# Reactrobe.net
KiCad netlist of a schematic drawn in EAGLE
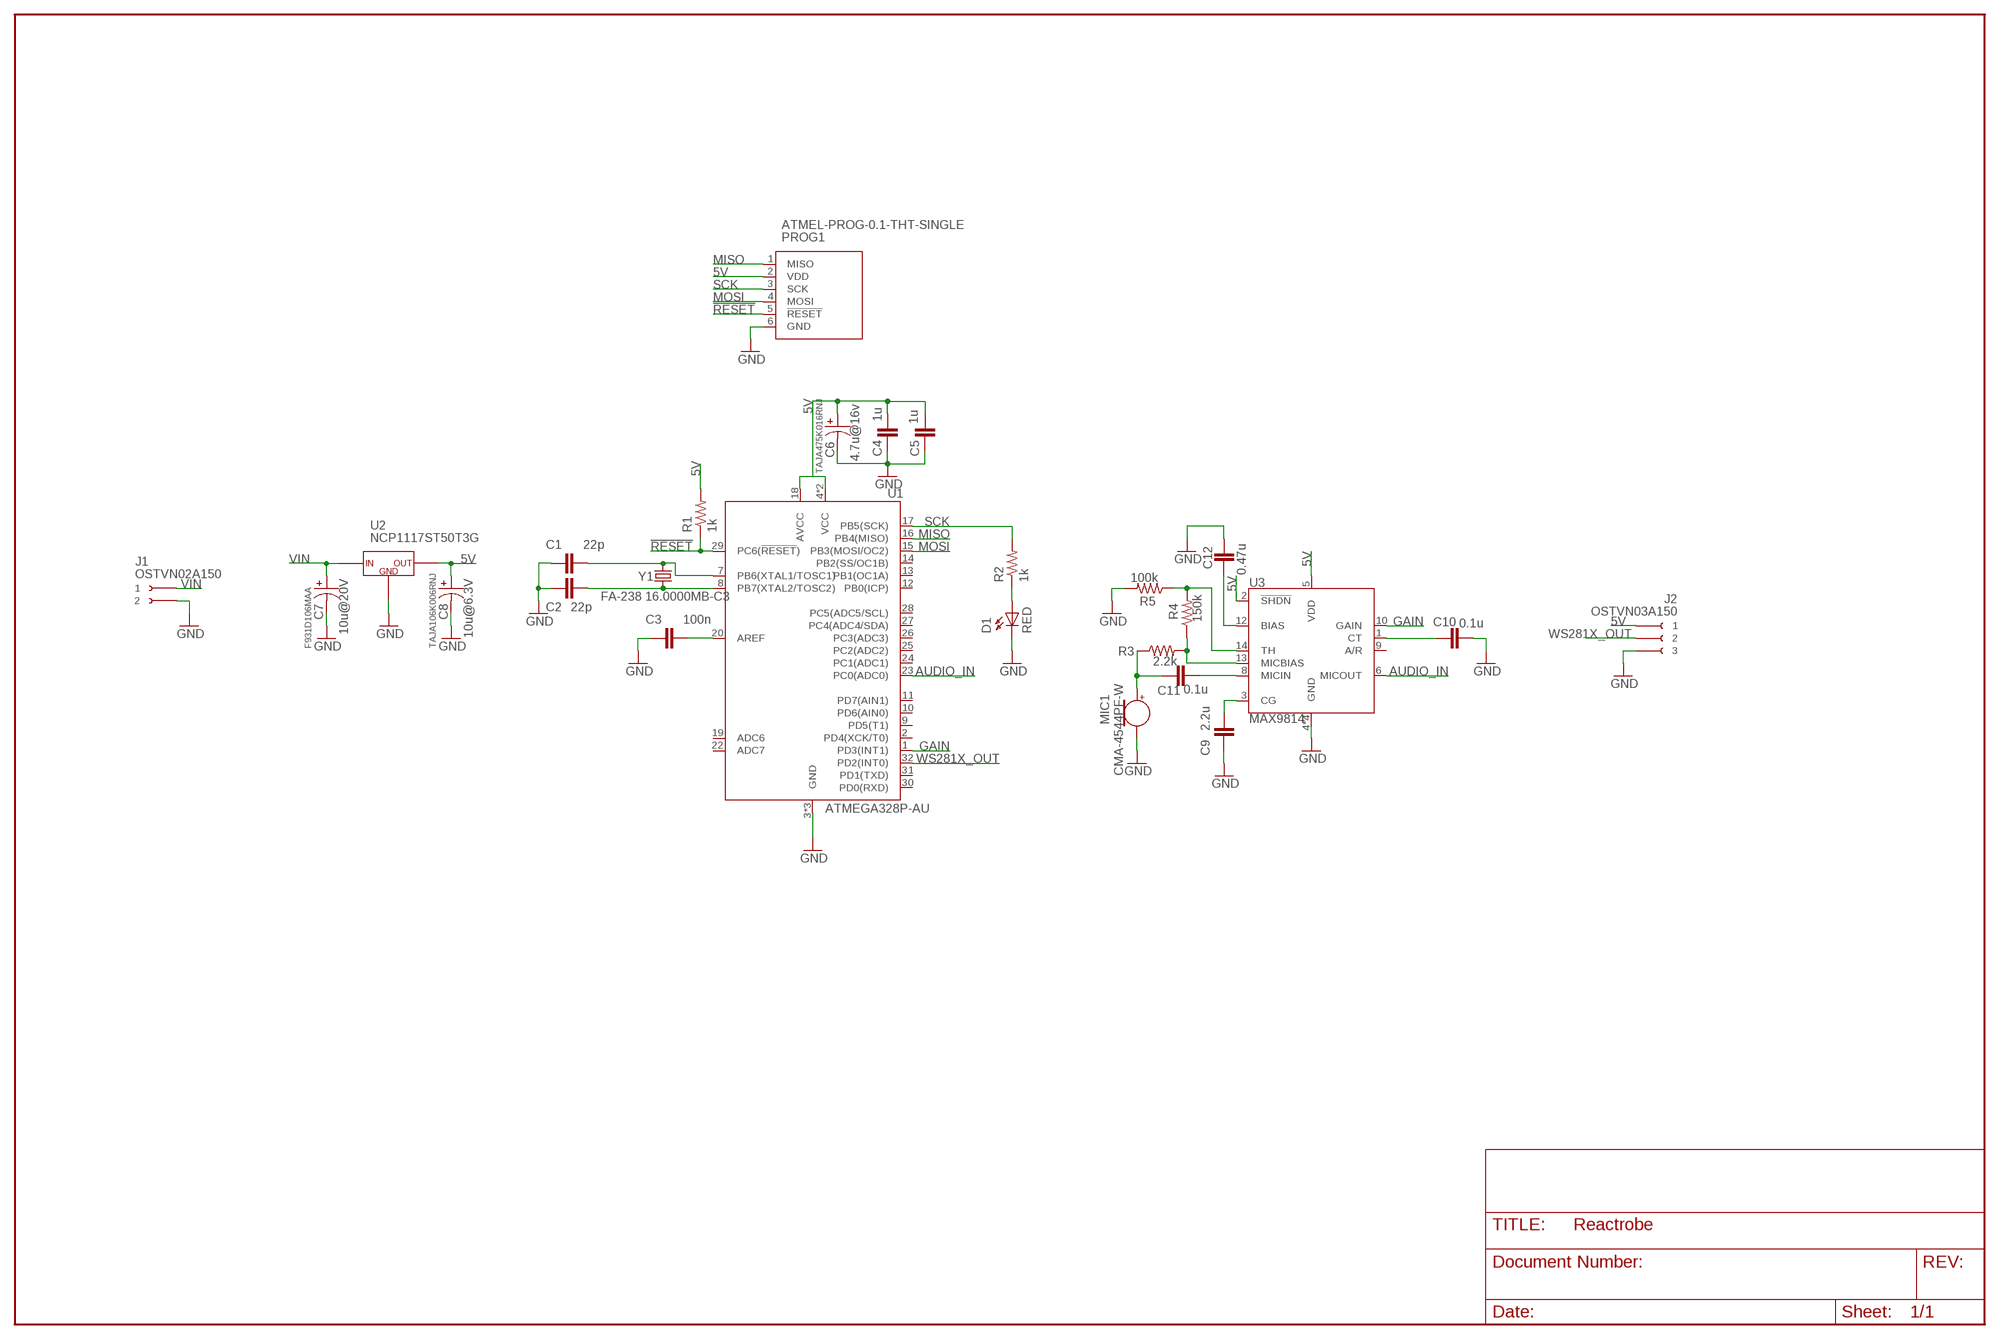
[diagram p0: schematic, sheet 1]

(export (version "E")
  (design (tool "Eeschema 10.0.6"))
  (components
    (comp (ref "C1")
      (value "22p")
      (footprint "eagle-import:C0603")
      (libsource (lib "eagle-import") (part "CAP-CER-SMD0603"))
    )
    (comp (ref "C2")
      (value "22p")
      (footprint "eagle-import:C0603")
      (libsource (lib "eagle-import") (part "CAP-CER-SMD0603"))
    )
    (comp (ref "C3")
      (value "100n")
      (footprint "eagle-import:C0603")
      (libsource (lib "eagle-import") (part "CAP-CER-SMD0603"))
    )
    (comp (ref "C4")
      (value "1u")
      (footprint "eagle-import:C0603")
      (libsource (lib "eagle-import") (part "CAP-CER-SMD0603"))
    )
    (comp (ref "C5")
      (value "1u")
      (footprint "eagle-import:C0603")
      (libsource (lib "eagle-import") (part "CAP-CER-SMD0603"))
    )
    (comp (ref "C6")
      (value "4.7u@16v")
      (footprint "eagle-import:CAPMP3216X160")
      (libsource (lib "eagle-import") (part "CAP-TANT-SMD1206"))
    )
    (comp (ref "C7")
      (value "10u@20V")
      (footprint "eagle-import:CAPMP3216X160")
      (libsource (lib "eagle-import") (part "CAP-TANT-SMD1206"))
    )
    (comp (ref "C8")
      (value "10u@6.3V")
      (footprint "eagle-import:CAPMP3216X160")
      (libsource (lib "eagle-import") (part "CAP-TANT-SMD1206"))
    )
    (comp (ref "C9")
      (value "2.2u")
      (footprint "eagle-import:C0603")
      (libsource (lib "eagle-import") (part "CAP-CER-SMD0603"))
    )
    (comp (ref "C10")
      (value "0.1u")
      (footprint "eagle-import:C0603")
      (libsource (lib "eagle-import") (part "CAP-CER-SMD0603"))
    )
    (comp (ref "C11")
      (value "0.1u")
      (footprint "eagle-import:C0603")
      (libsource (lib "eagle-import") (part "CAP-CER-SMD0603"))
    )
    (comp (ref "C12")
      (value "0.47u")
      (footprint "eagle-import:C0603")
      (libsource (lib "eagle-import") (part "CAP-CER-SMD0603"))
    )
    (comp (ref "D1")
      (value "RED")
      (footprint "eagle-import:CHIP-LED0603")
      (libsource (lib "eagle-import") (part "LED-0603"))
    )
    (comp (ref "J1")
      (value "OSTVN02A150")
      (footprint "eagle-import:OSTVN02A150")
      (libsource (lib "eagle-import") (part "OSTVN02A150"))
    )
    (comp (ref "J2")
      (value "OSTVN03A150")
      (footprint "eagle-import:OSTVN03A150")
      (libsource (lib "eagle-import") (part "OSTVN03A150"))
    )
    (comp (ref "MIC1")
      (value "CMA-4544PF-W")
      (footprint "eagle-import:MIC_CMA-4544PF-W")
      (libsource (lib "eagle-import") (part "CMA-4544PF-W"))
    )
    (comp (ref "PROG1")
      (value "ATMEL-PROG-0.1-THT-SINGLE")
      (footprint "eagle-import:HEADER-0.1-6")
      (libsource (lib "eagle-import") (part "ATMEL-PROG-0.1-THT-SINGLE"))
    )
    (comp (ref "R1")
      (value "1k")
      (footprint "eagle-import:R0603")
      (libsource (lib "eagle-import") (part "RES-SMD0603"))
    )
    (comp (ref "R2")
      (value "1k")
      (footprint "eagle-import:R0603")
      (libsource (lib "eagle-import") (part "RES-SMD0603"))
    )
    (comp (ref "R3")
      (value "2.2k")
      (footprint "eagle-import:R0603")
      (libsource (lib "eagle-import") (part "RES-SMD0603"))
    )
    (comp (ref "R4")
      (value "150k")
      (footprint "eagle-import:R0603")
      (libsource (lib "eagle-import") (part "RES-SMD0603"))
    )
    (comp (ref "R5")
      (value "100k")
      (footprint "eagle-import:R0603")
      (libsource (lib "eagle-import") (part "RES-SMD0603"))
    )
    (comp (ref "U1")
      (value "ATMEGA328P-AU")
      (footprint "eagle-import:QFP80P900X900X120-32")
      (libsource (lib "eagle-import") (part "ATMEGA328P-AU"))
    )
    (comp (ref "U2")
      (value "NCP1117ST50T3G")
      (footprint "eagle-import:SOT223")
      (libsource (lib "eagle-import") (part "NCP1117ST50T3G"))
    )
    (comp (ref "U3")
      (value "MAX9814")
      (footprint "eagle-import:SON40P300X300X80-15T170X230")
      (libsource (lib "eagle-import") (part "MAX9814"))
    )
    (comp (ref "Y1")
      (value "FA-238 16.0000MB-C3")
      (footprint "eagle-import:OSCCC320X250X70")
      (libsource (lib "eagle-import") (part "CRYSTAL-SMD-43.2X2.5L"))
    )
  )
  (nets
    (net (code "1") (name "/5V") (class "Default")
      (node (ref "C4") (pin "2") (pinfunction "2_2") (pintype "passive"))
      (node (ref "C5") (pin "2") (pinfunction "2_2") (pintype "passive"))
      (node (ref "C6") (pin "A") (pinfunction "A_A") (pintype "passive"))
      (node (ref "C8") (pin "A") (pinfunction "A_A") (pintype "passive"))
      (node (ref "J2") (pin "P$1") (pinfunction "1_P$1") (pintype "passive"))
      (node (ref "PROG1") (pin "2") (pinfunction "VDD_2") (pintype "passive"))
      (node (ref "R1") (pin "2") (pinfunction "2_2") (pintype "passive"))
      (node (ref "U1") (pin "18") (pinfunction "AVCC_18") (pintype "passive"))
      (node (ref "U1") (pin "4") (pinfunction "VCC_4") (pintype "passive"))
      (node (ref "U1") (pin "6") (pinfunction "VCC_6") (pintype "passive"))
      (node (ref "U2") (pin "2") (pinfunction "OUT_2") (pintype "passive"))
      (node (ref "U3") (pin "2") (pinfunction "~{SHDN}_2") (pintype "passive"))
      (node (ref "U3") (pin "5") (pinfunction "VDD_5") (pintype "passive"))
    )
    (net (code "2") (name "/AUDIO_IN") (class "Default")
      (node (ref "U1") (pin "23") (pinfunction "PC0(ADC0)_23") (pintype "passive"))
      (node (ref "U3") (pin "6") (pinfunction "MICOUT_6") (pintype "passive"))
    )
    (net (code "3") (name "/GAIN") (class "Default")
      (node (ref "U1") (pin "1") (pinfunction "PD3(INT1)_1") (pintype "passive"))
      (node (ref "U3") (pin "10") (pinfunction "GAIN_10") (pintype "passive"))
    )
    (net (code "4") (name "/MISO") (class "Default")
      (node (ref "PROG1") (pin "1") (pinfunction "MISO_1") (pintype "passive"))
      (node (ref "U1") (pin "16") (pinfunction "PB4(MISO)_16") (pintype "passive"))
    )
    (net (code "5") (name "/MOSI") (class "Default")
      (node (ref "PROG1") (pin "4") (pinfunction "MOSI_4") (pintype "passive"))
      (node (ref "U1") (pin "15") (pinfunction "PB3(MOSI/OC2)_15") (pintype "passive"))
    )
    (net (code "6") (name "/SCK") (class "Default")
      (node (ref "PROG1") (pin "3") (pinfunction "SCK_3") (pintype "passive"))
      (node (ref "R2") (pin "2") (pinfunction "2_2") (pintype "passive"))
      (node (ref "U1") (pin "17") (pinfunction "PB5(SCK)_17") (pintype "passive"))
    )
    (net (code "7") (name "/VIN") (class "Default")
      (node (ref "C7") (pin "A") (pinfunction "A_A") (pintype "passive"))
      (node (ref "J1") (pin "P$1") (pinfunction "1_P$1") (pintype "passive"))
      (node (ref "U2") (pin "3") (pinfunction "IN_3") (pintype "passive"))
    )
    (net (code "8") (name "/WS281X_OUT") (class "Default")
      (node (ref "J2") (pin "P$2") (pinfunction "2_P$2") (pintype "passive"))
      (node (ref "U1") (pin "32") (pinfunction "PD2(INT0)_32") (pintype "passive"))
    )
    (net (code "9") (name "/~{RESET}") (class "Default")
      (node (ref "PROG1") (pin "5") (pinfunction "~{RESET}_5") (pintype "passive"))
      (node (ref "R1") (pin "1") (pinfunction "1_1") (pintype "passive"))
      (node (ref "U1") (pin "29") (pinfunction "PC6(~{RESET})_29") (pintype "passive"))
    )
    (net (code "10") (name "GND") (class "Default")
      (node (ref "C1") (pin "1") (pinfunction "1_1") (pintype "passive"))
      (node (ref "C10") (pin "1") (pinfunction "1_1") (pintype "passive"))
      (node (ref "C12") (pin "1") (pinfunction "1_1") (pintype "passive"))
      (node (ref "C2") (pin "1") (pinfunction "1_1") (pintype "passive"))
      (node (ref "C3") (pin "1") (pinfunction "1_1") (pintype "passive"))
      (node (ref "C4") (pin "1") (pinfunction "1_1") (pintype "passive"))
      (node (ref "C5") (pin "1") (pinfunction "1_1") (pintype "passive"))
      (node (ref "C6") (pin "C") (pinfunction "C_C") (pintype "passive"))
      (node (ref "C7") (pin "C") (pinfunction "C_C") (pintype "passive"))
      (node (ref "C8") (pin "C") (pinfunction "C_C") (pintype "passive"))
      (node (ref "C9") (pin "1") (pinfunction "1_1") (pintype "passive"))
      (node (ref "D1") (pin "C") (pinfunction "K_C") (pintype "passive"))
      (node (ref "J1") (pin "P$2") (pinfunction "2_P$2") (pintype "passive"))
      (node (ref "J2") (pin "P$3") (pinfunction "3_P$3") (pintype "passive"))
      (node (ref "MIC1") (pin "2") (pinfunction "N_2") (pintype "passive"))
      (node (ref "PROG1") (pin "6") (pinfunction "GND_6") (pintype "passive"))
      (node (ref "R5") (pin "2") (pinfunction "2_2") (pintype "passive"))
      (node (ref "U1") (pin "21") (pinfunction "GND_21") (pintype "passive"))
      (node (ref "U1") (pin "3") (pinfunction "GND_3") (pintype "passive"))
      (node (ref "U1") (pin "5") (pinfunction "GND_5") (pintype "passive"))
      (node (ref "U2") (pin "1") (pinfunction "GND_1") (pintype "passive"))
      (node (ref "U3") (pin "11") (pinfunction "GND_11") (pintype "passive"))
      (node (ref "U3") (pin "15") (pinfunction "GND_15") (pintype "passive"))
      (node (ref "U3") (pin "4") (pinfunction "GND_4") (pintype "passive"))
      (node (ref "U3") (pin "7") (pinfunction "GND_7") (pintype "passive"))
    )
    (net (code "11") (name "Net-(D1-PadA)") (class "Default")
      (node (ref "D1") (pin "A") (pinfunction "A_A") (pintype "passive"))
      (node (ref "R2") (pin "1") (pinfunction "1_1") (pintype "passive"))
    )
    (net (code "12") (name "Net-(MIC1-P)") (class "Default")
      (node (ref "C11") (pin "2") (pinfunction "2_2") (pintype "passive"))
      (node (ref "MIC1") (pin "1") (pinfunction "P_1") (pintype "passive"))
      (node (ref "R3") (pin "1") (pinfunction "1_1") (pintype "passive"))
    )
    (net (code "13") (name "Net-(U1-AREF)") (class "Default")
      (node (ref "C3") (pin "2") (pinfunction "2_2") (pintype "passive"))
      (node (ref "U1") (pin "20") (pinfunction "AREF_20") (pintype "passive"))
    )
    (net (code "14") (name "Net-(U1-PB6(XTAL1{slash}TOSC1))") (class "Default")
      (node (ref "C1") (pin "2") (pinfunction "2_2") (pintype "passive"))
      (node (ref "U1") (pin "7") (pinfunction "PB6(XTAL1/TOSC1)_7") (pintype "passive"))
      (node (ref "Y1") (pin "3") (pinfunction "2_3") (pintype "passive"))
    )
    (net (code "15") (name "Net-(U1-PB7(XTAL2{slash}TOSC2))") (class "Default")
      (node (ref "C2") (pin "2") (pinfunction "2_2") (pintype "passive"))
      (node (ref "U1") (pin "8") (pinfunction "PB7(XTAL2/TOSC2)_8") (pintype "passive"))
      (node (ref "Y1") (pin "1") (pinfunction "1_1") (pintype "passive"))
    )
    (net (code "16") (name "Net-(U3-BIAS)") (class "Default")
      (node (ref "C12") (pin "2") (pinfunction "2_2") (pintype "passive"))
      (node (ref "U3") (pin "12") (pinfunction "BIAS_12") (pintype "passive"))
    )
    (net (code "17") (name "Net-(U3-CG)") (class "Default")
      (node (ref "C9") (pin "2") (pinfunction "2_2") (pintype "passive"))
      (node (ref "U3") (pin "3") (pinfunction "CG_3") (pintype "passive"))
    )
    (net (code "18") (name "Net-(U3-CT)") (class "Default")
      (node (ref "C10") (pin "2") (pinfunction "2_2") (pintype "passive"))
      (node (ref "U3") (pin "1") (pinfunction "CT_1") (pintype "passive"))
    )
    (net (code "19") (name "Net-(U3-MICBIAS)") (class "Default")
      (node (ref "R3") (pin "2") (pinfunction "2_2") (pintype "passive"))
      (node (ref "R4") (pin "1") (pinfunction "1_1") (pintype "passive"))
      (node (ref "U3") (pin "13") (pinfunction "MICBIAS_13") (pintype "passive"))
    )
    (net (code "20") (name "Net-(U3-MICIN)") (class "Default")
      (node (ref "C11") (pin "1") (pinfunction "1_1") (pintype "passive"))
      (node (ref "U3") (pin "8") (pinfunction "MICIN_8") (pintype "passive"))
    )
    (net (code "21") (name "Net-(U3-TH)") (class "Default")
      (node (ref "R4") (pin "2") (pinfunction "2_2") (pintype "passive"))
      (node (ref "R5") (pin "1") (pinfunction "1_1") (pintype "passive"))
      (node (ref "U3") (pin "14") (pinfunction "TH_14") (pintype "passive"))
    )
    (net (code "22") (name "unconnected-(U1-ADC6-Pad19)") (class "Default")
      (node (ref "U1") (pin "19") (pinfunction "ADC6_19") (pintype "passive"))
    )
    (net (code "23") (name "unconnected-(U1-ADC7-Pad22)") (class "Default")
      (node (ref "U1") (pin "22") (pinfunction "ADC7_22") (pintype "passive"))
    )
    (net (code "24") (name "unconnected-(U1-PB0(ICP)-Pad12)") (class "Default")
      (node (ref "U1") (pin "12") (pinfunction "PB0(ICP)_12") (pintype "passive"))
    )
    (net (code "25") (name "unconnected-(U1-PB1(OC1A)-Pad13)") (class "Default")
      (node (ref "U1") (pin "13") (pinfunction "PB1(OC1A)_13") (pintype "passive"))
    )
    (net (code "26") (name "unconnected-(U1-PB2(SS{slash}OC1B)-Pad14)") (class "Default")
      (node (ref "U1") (pin "14") (pinfunction "PB2(SS/OC1B)_14") (pintype "passive"))
    )
    (net (code "27") (name "unconnected-(U1-PC1(ADC1)-Pad24)") (class "Default")
      (node (ref "U1") (pin "24") (pinfunction "PC1(ADC1)_24") (pintype "passive"))
    )
    (net (code "28") (name "unconnected-(U1-PC2(ADC2)-Pad25)") (class "Default")
      (node (ref "U1") (pin "25") (pinfunction "PC2(ADC2)_25") (pintype "passive"))
    )
    (net (code "29") (name "unconnected-(U1-PC3(ADC3)-Pad26)") (class "Default")
      (node (ref "U1") (pin "26") (pinfunction "PC3(ADC3)_26") (pintype "passive"))
    )
    (net (code "30") (name "unconnected-(U1-PC4(ADC4{slash}SDA)-Pad27)") (class "Default")
      (node (ref "U1") (pin "27") (pinfunction "PC4(ADC4/SDA)_27") (pintype "passive"))
    )
    (net (code "31") (name "unconnected-(U1-PC5(ADC5{slash}SCL)-Pad28)") (class "Default")
      (node (ref "U1") (pin "28") (pinfunction "PC5(ADC5/SCL)_28") (pintype "passive"))
    )
    (net (code "32") (name "unconnected-(U1-PD0(RXD)-Pad30)") (class "Default")
      (node (ref "U1") (pin "30") (pinfunction "PD0(RXD)_30") (pintype "passive"))
    )
    (net (code "33") (name "unconnected-(U1-PD1(TXD)-Pad31)") (class "Default")
      (node (ref "U1") (pin "31") (pinfunction "PD1(TXD)_31") (pintype "passive"))
    )
    (net (code "34") (name "unconnected-(U1-PD4(XCK{slash}T0)-Pad2)") (class "Default")
      (node (ref "U1") (pin "2") (pinfunction "PD4(XCK/T0)_2") (pintype "passive"))
    )
    (net (code "35") (name "unconnected-(U1-PD5(T1)-Pad9)") (class "Default")
      (node (ref "U1") (pin "9") (pinfunction "PD5(T1)_9") (pintype "passive"))
    )
    (net (code "36") (name "unconnected-(U1-PD6(AIN0)-Pad10)") (class "Default")
      (node (ref "U1") (pin "10") (pinfunction "PD6(AIN0)_10") (pintype "passive"))
    )
    (net (code "37") (name "unconnected-(U1-PD7(AIN1)-Pad11)") (class "Default")
      (node (ref "U1") (pin "11") (pinfunction "PD7(AIN1)_11") (pintype "passive"))
    )
    (net (code "38") (name "unconnected-(U3-A{slash}R-Pad9)") (class "Default")
      (node (ref "U3") (pin "9") (pinfunction "A/R_9") (pintype "passive"))
    )
  )
)
